# Laser_Driver_v6_1.net
KiCad netlist of a schematic drawn in Altium Designer
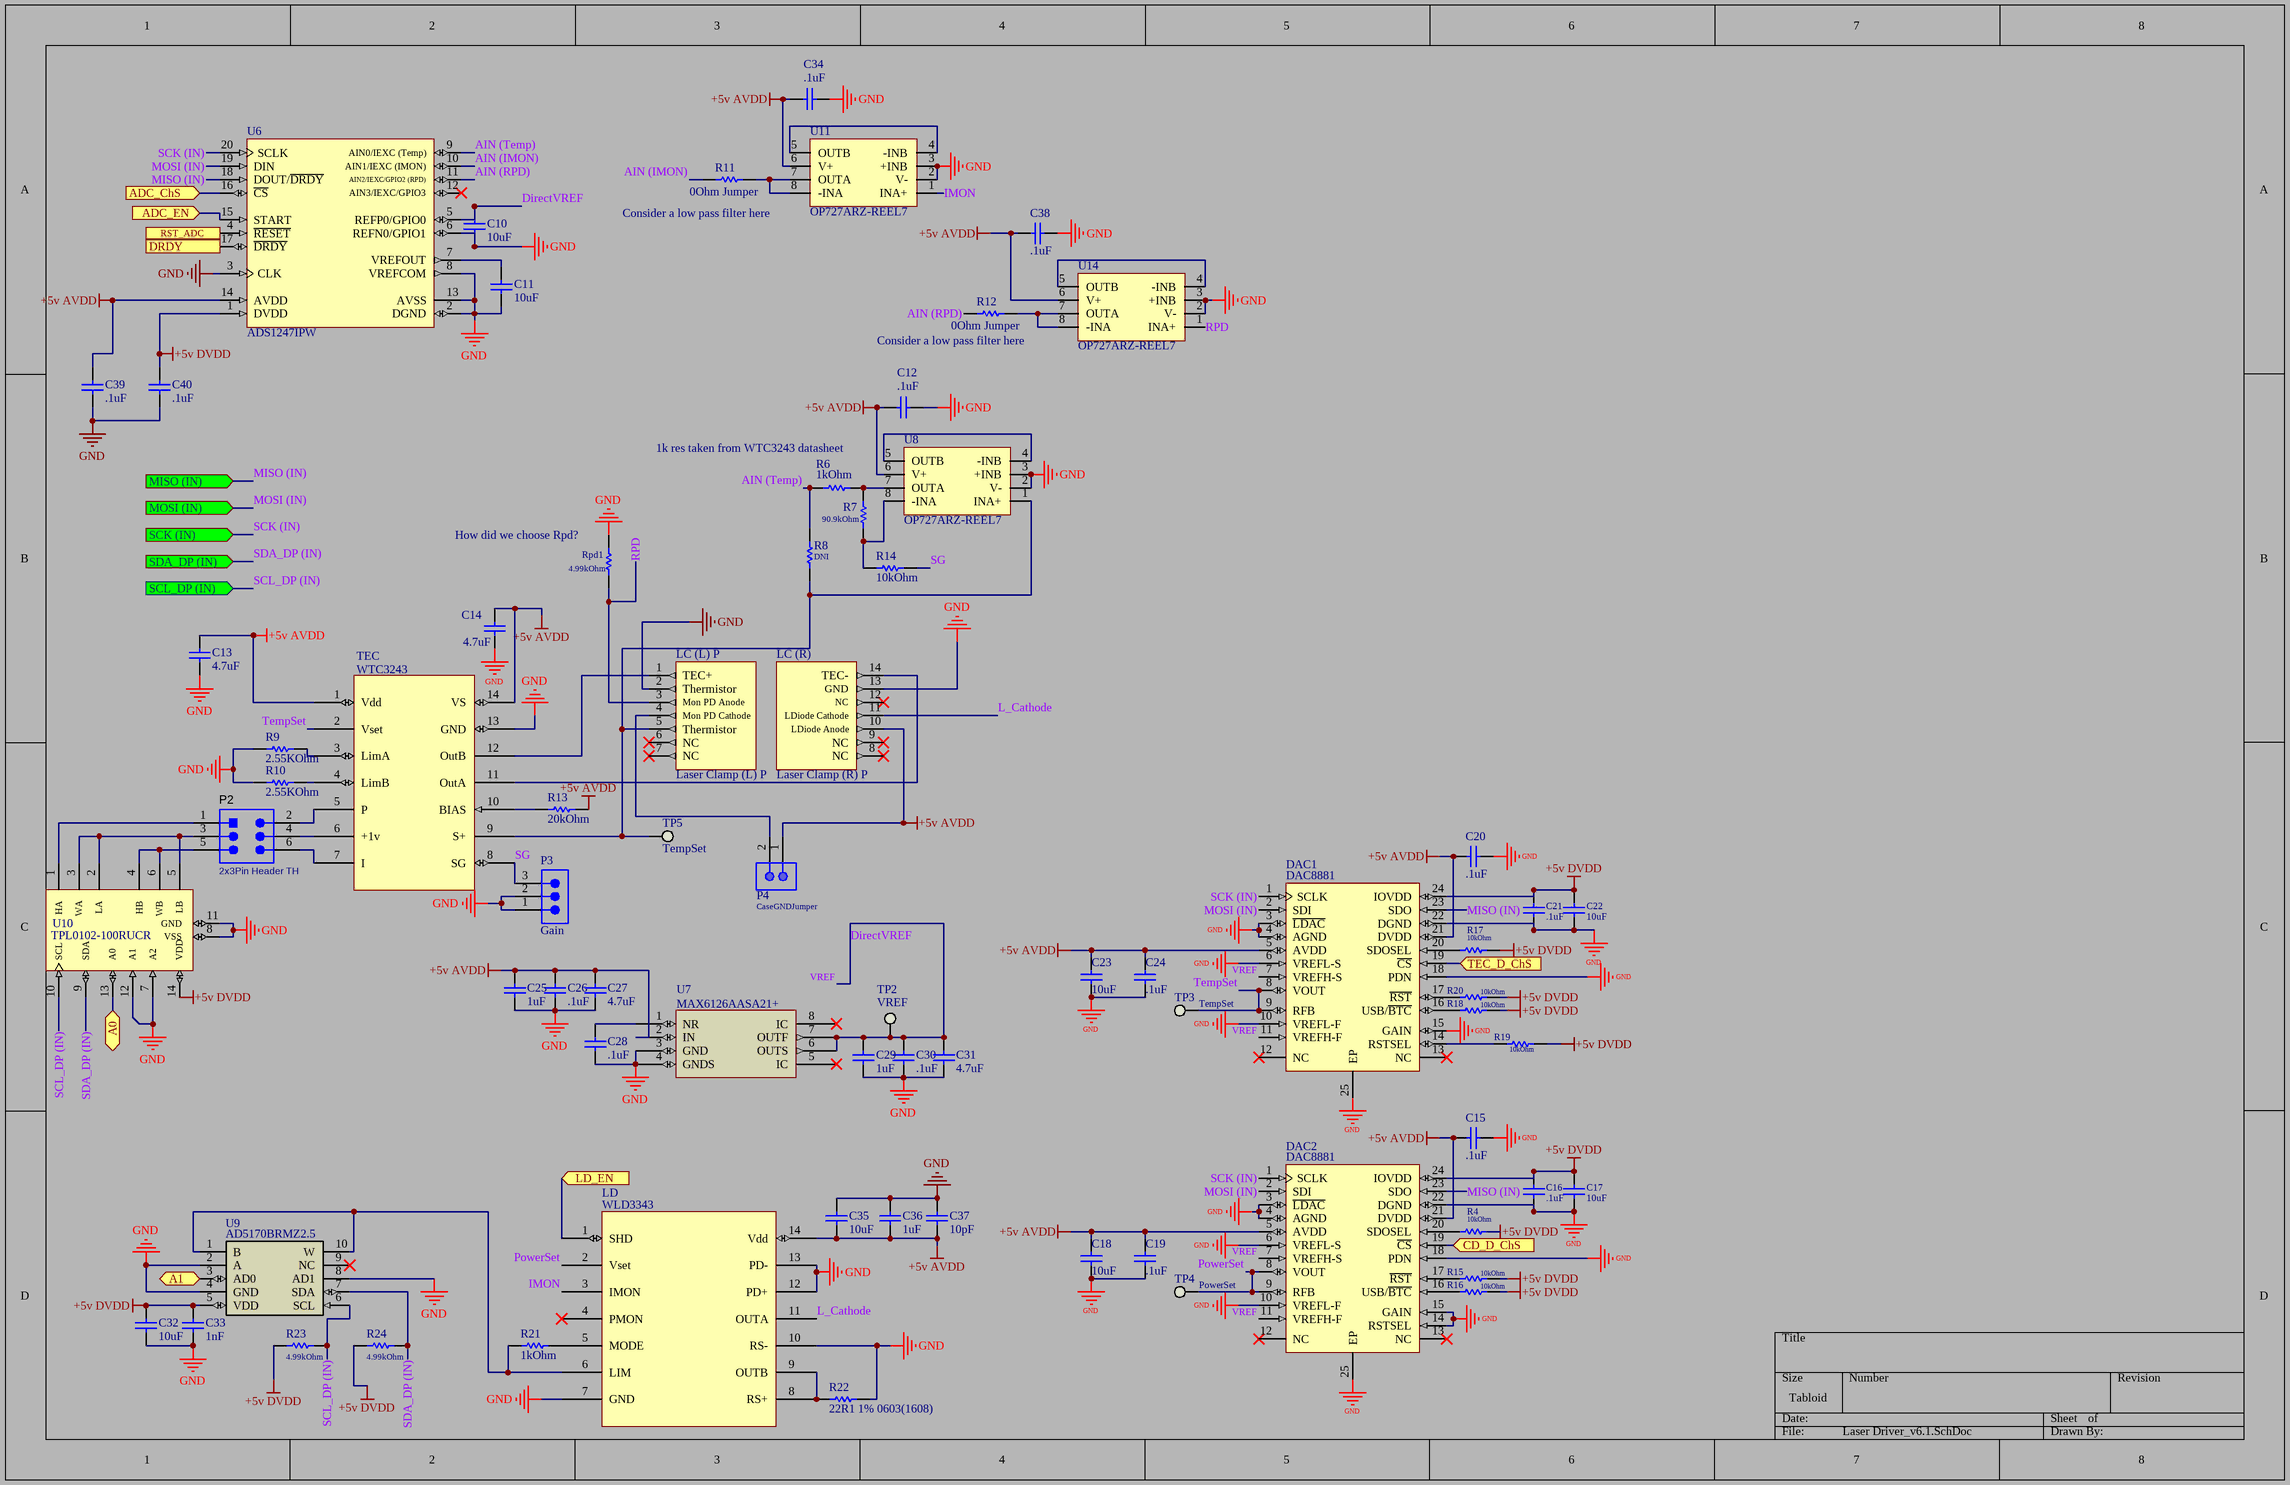
[diagram p0: Laser Driver_v6.1.SchDoc]

(export (version "E")
  (design (tool "Eeschema 10.0.6"))
  (components
    (comp (ref "C10")
      (value "10uF")
      (footprint "CAPC1608X90X35ML10T15")
      (fields (field (name "PART NUMBER") "GRM188R60G106ME47J") (field (name "MANUFACTURER") "Murata"))
      (libsource (lib "10uF Cap 0603") (part "CMP-2006-02549-1"))
    )
    (comp (ref "C11")
      (value "10uF")
      (footprint "CAPC1608X90X35ML10T15")
      (fields (field (name "PART NUMBER") "GRM188R60G106ME47J") (field (name "MANUFACTURER") "Murata"))
      (libsource (lib "10uF Cap 0603") (part "CMP-2006-02549-1"))
    )
    (comp (ref "C12")
      (value ".1uF")
      (footprint "CAPC1608X90X35ML15T15")
      (fields
        (field (name "PART NUMBER") "06033D104MAT2A")
        (field (name "MANUFACTURER") "AVX Interconnect / Elco")
      )
      (libsource (lib "0.1uF Cap 0603") (part "CMP-2006-04192-1"))
    )
    (comp (ref "C13")
      (value "4.7uF")
      (footprint "CAPC1608X90X35ML10T15")
      (description "Chip Capacitor, 4.7 uF, +/- 10%, 6.3 V, -55 to 85 degC, 0603 (1608 Metric), RoHS, Tape and Reel")
      (fields (field (name "PARTNUMBER") "GRM188R60J475KE19D") (field (name "TOLERANCE") "10%"))
      (libsource (lib "4.7uF Cap 0603") (part "CMP-2006-02799-2"))
    )
    (comp (ref "C14")
      (value "4.7uF")
      (footprint "CAPC1608X90X35ML10T15")
      (description "Chip Capacitor, 4.7 uF, +/- 10%, 6.3 V, -55 to 85 degC, 0603 (1608 Metric), RoHS, Tape and Reel")
      (fields (field (name "PARTNUMBER") "GRM188R60J475KE19D") (field (name "TOLERANCE") "10%"))
      (libsource (lib "4.7uF Cap 0603") (part "CMP-2006-02799-2"))
    )
    (comp (ref "C15")
      (value ".1uF")
      (footprint "CAPC1608X90X35ML15T15")
      (fields
        (field (name "PART NUMBER") "06033D104MAT2A")
        (field (name "MANUFACTURER") "AVX Interconnect / Elco")
      )
      (libsource (lib "0.1uF Cap 0603") (part "CMP-2006-04192-1"))
    )
    (comp (ref "C16")
      (value ".1uF")
      (footprint "CAPC1608X90X35ML15T15")
      (fields
        (field (name "PART NUMBER") "06033D104MAT2A")
        (field (name "MANUFACTURER") "AVX Interconnect / Elco")
      )
      (libsource (lib "0.1uF Cap 0603") (part "CMP-2006-04192-1"))
    )
    (comp (ref "C17")
      (value "10uF")
      (footprint "CAPC1608X90X35ML10T15")
      (fields (field (name "PART NUMBER") "GRM188R60G106ME47J") (field (name "MANUFACTURER") "Murata"))
      (libsource (lib "10uF Cap 0603") (part "CMP-2006-02549-1"))
    )
    (comp (ref "C18")
      (value "10uF")
      (footprint "CAPC1608X90X35ML10T15")
      (fields (field (name "PART NUMBER") "GRM188R60G106ME47J") (field (name "MANUFACTURER") "Murata"))
      (libsource (lib "10uF Cap 0603") (part "CMP-2006-02549-1"))
    )
    (comp (ref "C19")
      (value ".1uF")
      (footprint "CAPC1608X90X35ML15T15")
      (fields
        (field (name "PART NUMBER") "06033D104MAT2A")
        (field (name "MANUFACTURER") "AVX Interconnect / Elco")
      )
      (libsource (lib "0.1uF Cap 0603") (part "CMP-2006-04192-1"))
    )
    (comp (ref "C20")
      (value ".1uF")
      (footprint "CAPC1608X90X35ML15T15")
      (fields
        (field (name "PART NUMBER") "06033D104MAT2A")
        (field (name "MANUFACTURER") "AVX Interconnect / Elco")
      )
      (libsource (lib "0.1uF Cap 0603") (part "CMP-2006-04192-1"))
    )
    (comp (ref "C21")
      (value ".1uF")
      (footprint "CAPC1608X90X35ML15T15")
      (fields
        (field (name "PART NUMBER") "06033D104MAT2A")
        (field (name "MANUFACTURER") "AVX Interconnect / Elco")
      )
      (libsource (lib "0.1uF Cap 0603") (part "CMP-2006-04192-1"))
    )
    (comp (ref "C22")
      (value "10uF")
      (footprint "CAPC1608X90X35ML10T15")
      (fields (field (name "PART NUMBER") "GRM188R60G106ME47J") (field (name "MANUFACTURER") "Murata"))
      (libsource (lib "10uF Cap 0603") (part "CMP-2006-02549-1"))
    )
    (comp (ref "C23")
      (value "10uF")
      (footprint "CAPC1608X90X35ML10T15")
      (fields (field (name "PART NUMBER") "GRM188R60G106ME47J") (field (name "MANUFACTURER") "Murata"))
      (libsource (lib "10uF Cap 0603") (part "CMP-2006-02549-1"))
    )
    (comp (ref "C24")
      (value ".1uF")
      (footprint "CAPC1608X90X35ML15T15")
      (fields
        (field (name "PART NUMBER") "06033D104MAT2A")
        (field (name "MANUFACTURER") "AVX Interconnect / Elco")
      )
      (libsource (lib "0.1uF Cap 0603") (part "CMP-2006-04192-1"))
    )
    (comp (ref "C25")
      (value "1uF")
      (footprint "CAPC1608X90X35ML15T15")
      (fields
        (field (name "PART NUMBER") "06036D105KAT2A")
        (field (name "MANUFACTURER") "AVX Interconnect / Elco")
      )
      (libsource (lib "1uF Cap 0603") (part "CMP-2006-04474-1"))
    )
    (comp (ref "C26")
      (value ".1uF")
      (footprint "CAPC1608X90X35ML15T15")
      (fields
        (field (name "PART NUMBER") "06033D104MAT2A")
        (field (name "MANUFACTURER") "AVX Interconnect / Elco")
      )
      (libsource (lib "0.1uF Cap 0603") (part "CMP-2006-04192-1"))
    )
    (comp (ref "C27")
      (value "4.7uF")
      (footprint "CAPC1608X90X35ML10T15")
      (description "Chip Capacitor, 4.7 uF, +/- 10%, 6.3 V, -55 to 85 degC, 0603 (1608 Metric), RoHS, Tape and Reel")
      (fields (field (name "PARTNUMBER") "GRM188R60J475KE19D") (field (name "TOLERANCE") "10%"))
      (libsource (lib "4.7uF Cap 0603") (part "CMP-2006-02799-2"))
    )
    (comp (ref "C28")
      (value ".1uF")
      (footprint "CAPC1608X90X35ML15T15")
      (fields
        (field (name "PART NUMBER") "06033D104MAT2A")
        (field (name "MANUFACTURER") "AVX Interconnect / Elco")
      )
      (libsource (lib "0.1uF Cap 0603") (part "CMP-2006-04192-1"))
    )
    (comp (ref "C29")
      (value "1uF")
      (footprint "CAPC1608X90X35ML15T15")
      (fields
        (field (name "PART NUMBER") "06036D105KAT2A")
        (field (name "MANUFACTURER") "AVX Interconnect / Elco")
      )
      (libsource (lib "1uF Cap 0603") (part "CMP-2006-04474-1"))
    )
    (comp (ref "C30")
      (value ".1uF")
      (footprint "CAPC1608X90X35ML15T15")
      (fields
        (field (name "PART NUMBER") "06033D104MAT2A")
        (field (name "MANUFACTURER") "AVX Interconnect / Elco")
      )
      (libsource (lib "0.1uF Cap 0603") (part "CMP-2006-04192-1"))
    )
    (comp (ref "C31")
      (value "4.7uF")
      (footprint "CAPC1608X90X35ML10T15")
      (description "Chip Capacitor, 4.7 uF, +/- 10%, 6.3 V, -55 to 85 degC, 0603 (1608 Metric), RoHS, Tape and Reel")
      (fields (field (name "PARTNUMBER") "GRM188R60J475KE19D") (field (name "TOLERANCE") "10%"))
      (libsource (lib "4.7uF Cap 0603") (part "CMP-2006-02799-2"))
    )
    (comp (ref "C32")
      (value "10uF")
      (footprint "CAPC1608X90X35ML10T15")
      (fields (field (name "PART NUMBER") "GRM188R60G106ME47J") (field (name "MANUFACTURER") "Murata"))
      (libsource (lib "10uF Cap 0603") (part "CMP-2006-02549-1"))
    )
    (comp (ref "C33")
      (value "1nF")
      (footprint "CAPC1608X90X35LL15T15")
      (fields
        (field (name "MANUFACTURER") "AVX Interconnect / Elco")
        (field (name "PART NUMBER") "06035C102KAT2A")
      )
      (libsource (lib "Altium Content Vault") (part "CAP"))
    )
    (comp (ref "C34")
      (value ".1uF")
      (footprint "CAPC1608X90X35ML15T15")
      (fields
        (field (name "PART NUMBER") "06033D104MAT2A")
        (field (name "MANUFACTURER") "AVX Interconnect / Elco")
      )
      (libsource (lib "0.1uF Cap 0603") (part "CMP-2006-04192-1"))
    )
    (comp (ref "C35")
      (value "10uF")
      (footprint "CAPC1608X90X35ML10T15")
      (fields (field (name "PART NUMBER") "GRM188R60G106ME47J") (field (name "MANUFACTURER") "Murata"))
      (libsource (lib "10uF Cap 0603") (part "CMP-2006-02549-1"))
    )
    (comp (ref "C36")
      (value "1uF")
      (footprint "CAPC1608X90X35ML15T15")
      (fields
        (field (name "PART NUMBER") "06036D105KAT2A")
        (field (name "MANUFACTURER") "AVX Interconnect / Elco")
      )
      (libsource (lib "1uF Cap 0603") (part "CMP-2006-04474-1"))
    )
    (comp (ref "C37")
      (value "10pF")
      (footprint "CAPC1608X90X35LL15T15")
      (fields
        (field (name "MANUFACTURER") "AVX Interconnect / Elco")
        (field (name "PART NUMBER") "06035A100DAT2A")
      )
      (libsource (lib "Altium Content Vault") (part "CAP"))
    )
    (comp (ref "C38")
      (value ".1uF")
      (footprint "CAPC1608X90X35ML15T15")
      (fields
        (field (name "PART NUMBER") "06033D104MAT2A")
        (field (name "MANUFACTURER") "AVX Interconnect / Elco")
      )
      (libsource (lib "0.1uF Cap 0603") (part "CMP-2006-04192-1"))
    )
    (comp (ref "C39")
      (value ".1uF")
      (footprint "CAPC1608X90X35ML15T15")
      (fields
        (field (name "PART NUMBER") "06033D104MAT2A")
        (field (name "MANUFACTURER") "AVX Interconnect / Elco")
      )
      (libsource (lib "0.1uF Cap 0603") (part "CMP-2006-04192-1"))
    )
    (comp (ref "C40")
      (value ".1uF")
      (footprint "CAPC1608X90X35ML15T15")
      (fields
        (field (name "PART NUMBER") "06033D104MAT2A")
        (field (name "MANUFACTURER") "AVX Interconnect / Elco")
      )
      (libsource (lib "0.1uF Cap 0603") (part "CMP-2006-04192-1"))
    )
    (comp (ref "DAC1")
      (value "DAC8881")
      (footprint "TI-RGE24-2450X2450TP_V")
      (fields (field (name "PARTNUMBER") "DAC8881SRGET") (field (name "MANUFACTURER") "Texas Instruments"))
      (libsource (lib "DAC8881") (part "CMP-0004-01437-1"))
    )
    (comp (ref "DAC2")
      (value "DAC8881")
      (footprint "TI-RGE24-2450X2450TP_V")
      (fields (field (name "PARTNUMBER") "DAC8881SRGET") (field (name "MANUFACTURER") "Texas Instruments"))
      (libsource (lib "DAC8881") (part "CMP-0004-01437-1"))
    )
    (comp (ref "LC (L) P")
      (value "Laser Clamp (L) P")
      (footprint "LaserClamp_L_Pump")
      (libsource (lib "LDv6") (part "Laser Clamp (L) Pump"))
    )
    (comp (ref "LC (R)")
      (value "Laser Clamp (R) P")
      (footprint "LaserClamp_R_Pump")
      (libsource (lib "LDv6") (part "Laser Clamp (R) Pump"))
    )
    (comp (ref "LD")
      (value "WLD3343")
      (footprint "LDv6:WLD3343")
      (description "Laser Current Driver")
      (libsource (lib "LDv6") (part "WLD3343"))
    )
    (comp (ref "P2")
      (value "2x3Pin Header TH")
      (footprint "SMTC-TSW-103-07-G-D_V")
      (fields (field (name "MANUFACTURER") "Samtec-Inc."))
      (libsource (lib "2x3 Pin Header TH 2.54") (part "CMP-2000-07329-1"))
    )
    (comp (ref "P3")
      (value "Gain")
      (footprint "SMTC-TSW-103-07-X-S")
      (description "0.025\" SQ Post Header, Through-hole, Vertical, -55 to 125 degC, 2.54 mm Pitch, 3-Pin, Male, RoHS")
      (fields (field (name "MANUFACTURER") "Samtec") (field (name "PARTNUMBER") "TSW-103-07-F-S"))
      (libsource (lib "3 Pin Header TH 2.54") (part "CMP-1024-00331-1"))
    )
    (comp (ref "P4")
      (value "CaseGNDJumper")
      (footprint "SMTC-TSW-102-07-S-S")
      (fields (field (name "MANUFACTURER") "Samtec"))
      (libsource (lib "2 Pin Header TH 2.54") (part "CMP-1681-00004-4"))
    )
    (comp (ref "R4")
      (value "10kOhm")
      (footprint "RESC1609X55X30LL15T15")
      (description "Chip Resistor, 10 KOhm, +/- 1%, 0.1 W, -55 to 155 degC, 0603 (1608 Metric), RoHS, Tape and Reel")
      (fields (field (name "TOLERANCE") "1%") (field (name "MANUFACTURER") "Panasonic"))
      (libsource (lib "10kOhm Res 0603") (part "CMP-2000-07452-1"))
    )
    (comp (ref "R6")
      (value "1kOhm")
      (footprint "RESC1609X50X30LL8T20")
      (description "Chip Resistor, 1 KOhm, +/- 1%, 0.1 W, -55 to 155 degC, 0603 (1608 Metric), RoHS, Tape and Reel")
      (fields (field (name "MANUFACTURER") "Vishay Semiconductor"))
      (libsource (lib "1kOhm Res 0603") (part "CMP-1666-00003-4"))
    )
    (comp (ref "R7")
      (value "90.9kOhm")
      (footprint "RESC1608X55X30NL15T15")
      (fields (field (name "MANUFACTURER") "Panasonic") (field (name "PART NUMBER") "ERJ-3EKF9092V"))
      (libsource (lib "90.9kOhm Res 0603") (part "CMP-2000-00680-1"))
    )
    (comp (ref "R8")
      (value "DNI")
      (footprint "RESC1608X55X25NL10T15")
      (description "Chip Resistor, 0 Ohm, +/- 5%, 0.1 W, -55 to 155 degC, 0603 (1608 Metric), RoHS, Tape and Reel")
      (fields (field (name "TOLERANCE") "5%") (field (name "MANUFACTURER") "Yageo"))
      (libsource (lib "0Ohm Jumper 0603") (part "CMP-2100-03667-1"))
    )
    (comp (ref "R9")
      (value "2.55KOhm")
      (footprint "RESC1608X55X25NL10T15")
      (fields (field (name "MANUFACTURER") "Yageo") (field (name "PART NUMBER") "RC0603FR-072K55L"))
      (libsource (lib "Altium Content Vault") (part "RES"))
    )
    (comp (ref "R10")
      (value "2.55KOhm")
      (footprint "RESC1608X55X25NL10T15")
      (fields (field (name "MANUFACTURER") "Yageo") (field (name "PART NUMBER") "RC0603FR-072K55L"))
      (libsource (lib "Altium Content Vault") (part "RES"))
    )
    (comp (ref "R11")
      (value "0Ohm Jumper")
      (footprint "RESC1608X55X25NL10T15")
      (description "Chip Resistor, 0 Ohm, +/- 5%, 0.1 W, -55 to 155 degC, 0603 (1608 Metric), RoHS, Tape and Reel")
      (fields (field (name "TOLERANCE") "5%") (field (name "MANUFACTURER") "Yageo"))
      (libsource (lib "0Ohm Jumper 0603") (part "CMP-2100-03667-1"))
    )
    (comp (ref "R12")
      (value "0Ohm Jumper")
      (footprint "RESC1608X55X25NL10T15")
      (description "Chip Resistor, 0 Ohm, +/- 5%, 0.1 W, -55 to 155 degC, 0603 (1608 Metric), RoHS, Tape and Reel")
      (fields (field (name "TOLERANCE") "5%") (field (name "MANUFACTURER") "Yageo"))
      (libsource (lib "0Ohm Jumper 0603") (part "CMP-2100-03667-1"))
    )
    (comp (ref "R13")
      (value "20kOhm")
      (footprint "RESC1608X55X25NL10T15")
      (description "Chip Resistor, 20 KOhm, +/- 1%, 0.1 W, -55 to 155 degC, 0603 (1608 Metric), RoHS, Tape and Reel")
      (fields (field (name "MANUFACTURER") "Yageo") (field (name "TOLERANCE") "1%"))
      (libsource (lib "20kOhm Res 0603") (part "CMP-2000-06932-1"))
    )
    (comp (ref "R14")
      (value "10kOhm")
      (footprint "RESC1609X55X30LL15T15")
      (description "Chip Resistor, 10 KOhm, +/- 1%, 0.1 W, -55 to 155 degC, 0603 (1608 Metric), RoHS, Tape and Reel")
      (fields (field (name "TOLERANCE") "1%") (field (name "MANUFACTURER") "Panasonic"))
      (libsource (lib "10kOhm Res 0603") (part "CMP-2000-07452-1"))
    )
    (comp (ref "R15")
      (value "10kOhm")
      (footprint "RESC1609X55X30LL15T15")
      (description "Chip Resistor, 10 KOhm, +/- 1%, 0.1 W, -55 to 155 degC, 0603 (1608 Metric), RoHS, Tape and Reel")
      (fields (field (name "TOLERANCE") "1%") (field (name "MANUFACTURER") "Panasonic"))
      (libsource (lib "10kOhm Res 0603") (part "CMP-2000-07452-1"))
    )
    (comp (ref "R16")
      (value "10kOhm")
      (footprint "RESC1609X55X30LL15T15")
      (description "Chip Resistor, 10 KOhm, +/- 1%, 0.1 W, -55 to 155 degC, 0603 (1608 Metric), RoHS, Tape and Reel")
      (fields (field (name "TOLERANCE") "1%") (field (name "MANUFACTURER") "Panasonic"))
      (libsource (lib "10kOhm Res 0603") (part "CMP-2000-07452-1"))
    )
    (comp (ref "R17")
      (value "10kOhm")
      (footprint "RESC1609X55X30LL15T15")
      (description "Chip Resistor, 10 KOhm, +/- 1%, 0.1 W, -55 to 155 degC, 0603 (1608 Metric), RoHS, Tape and Reel")
      (fields (field (name "TOLERANCE") "1%") (field (name "MANUFACTURER") "Panasonic"))
      (libsource (lib "10kOhm Res 0603") (part "CMP-2000-07452-1"))
    )
    (comp (ref "R18")
      (value "10kOhm")
      (footprint "RESC1609X55X30LL15T15")
      (description "Chip Resistor, 10 KOhm, +/- 1%, 0.1 W, -55 to 155 degC, 0603 (1608 Metric), RoHS, Tape and Reel")
      (fields (field (name "TOLERANCE") "1%") (field (name "MANUFACTURER") "Panasonic"))
      (libsource (lib "10kOhm Res 0603") (part "CMP-2000-07452-1"))
    )
    (comp (ref "R19")
      (value "10kOhm")
      (footprint "RESC1609X55X30LL15T15")
      (description "Chip Resistor, 10 KOhm, +/- 1%, 0.1 W, -55 to 155 degC, 0603 (1608 Metric), RoHS, Tape and Reel")
      (fields (field (name "TOLERANCE") "1%") (field (name "MANUFACTURER") "Panasonic"))
      (libsource (lib "10kOhm Res 0603") (part "CMP-2000-07452-1"))
    )
    (comp (ref "R20")
      (value "10kOhm")
      (footprint "RESC1609X55X30LL15T15")
      (description "Chip Resistor, 10 KOhm, +/- 1%, 0.1 W, -55 to 155 degC, 0603 (1608 Metric), RoHS, Tape and Reel")
      (fields (field (name "TOLERANCE") "1%") (field (name "MANUFACTURER") "Panasonic"))
      (libsource (lib "10kOhm Res 0603") (part "CMP-2000-07452-1"))
    )
    (comp (ref "R21")
      (value "1kOhm")
      (footprint "RESC1609X50X30LL8T20")
      (description "Chip Resistor, 1 KOhm, +/- 1%, 0.1 W, -55 to 155 degC, 0603 (1608 Metric), RoHS, Tape and Reel")
      (fields (field (name "MANUFACTURER") "Vishay Semiconductor"))
      (libsource (lib "1kOhm Res 0603") (part "CMP-1666-00003-4"))
    )
    (comp (ref "R22")
      (value "22R1 1% 0603(1608)")
      (footprint "RESC0603(1608)_M")
      (description "22R1 0.1W 1% 0603 (1608 Metric)  SMD")
      (fields (field (name "TOLERANCE") "1 %") (field (name "POWER") "0.1 W"))
      (libsource (lib "Altium Content Vault") (part "RES"))
    )
    (comp (ref "R23")
      (value "4.99kOhm")
      (footprint "RESC1608X55X30NL15T15")
      (fields (field (name "PART NUMBER") "ERJ-3EKF4991V") (field (name "MANUFACTURER") "Panasonic"))
      (libsource (lib "4.99kOhm Res 0603") (part "CMP-2000-00535-1"))
    )
    (comp (ref "R24")
      (value "4.99kOhm")
      (footprint "RESC1608X55X30NL15T15")
      (fields (field (name "PART NUMBER") "ERJ-3EKF4991V") (field (name "MANUFACTURER") "Panasonic"))
      (libsource (lib "4.99kOhm Res 0603") (part "CMP-2000-00535-1"))
    )
    (comp (ref "Rpd1")
      (value "4.99kOhm")
      (footprint "RESC1608X55X30NL15T15")
      (fields (field (name "PART NUMBER") "ERJ-3EKF4991V") (field (name "MANUFACTURER") "Panasonic"))
      (libsource (lib "4.99kOhm Res 0603") (part "CMP-2000-00535-1"))
    )
    (comp (ref "TEC")
      (value "WTC3243")
      (footprint "WTC3243")
      (description "TEC")
      (libsource (lib "LDv6") (part "WTC3243"))
    )
    (comp (ref "TP2")
      (value "VREF")
      (footprint "KSTN-5015_V")
      (description "Test Point, White, SMT")
      (fields (field (name "MANUFACTURER") "Keystone"))
      (libsource (lib "Test Point 2.66mm") (part "CMP-2000-05183-1"))
    )
    (comp (ref "TP3")
      (value "TempSet")
      (footprint "KSTN-5015_V")
      (description "Test Point, White, SMT")
      (fields (field (name "MANUFACTURER") "Keystone"))
      (libsource (lib "Test Point 2.66mm") (part "CMP-2000-05183-1"))
    )
    (comp (ref "TP4")
      (value "PowerSet")
      (footprint "KSTN-5015_V")
      (description "Test Point, White, SMT")
      (fields (field (name "MANUFACTURER") "Keystone"))
      (libsource (lib "Test Point 2.66mm") (part "CMP-2000-05183-1"))
    )
    (comp (ref "TP5")
      (value "TempSet")
      (footprint "KSTN-5015_V")
      (description "Test Point, White, SMT")
      (fields (field (name "MANUFACTURER") "Keystone"))
      (libsource (lib "Test Point 2.66mm") (part "CMP-2000-05183-1"))
    )
    (comp (ref "U6")
      (value "ADS1247IPW")
      (footprint "TI-PW20_N")
      (description "Low Noise, Precision 24-Bit ADC, -40 to 105 degC, 20-pin SOP (PW20), Green (RoHS & no Sb/Br)")
      (fields (field (name "MANUFACTURER") "Texas Instruments"))
      (libsource (lib "ADS1247") (part "CMP-0003-00815-2"))
    )
    (comp (ref "U7")
      (value "MAX6126AASA21+")
      (footprint "21-0041B_8")
      (description "No Description Available")
      (fields (field (name "COPYRIGHT") "Copyright (C) 2018 Accelerated Designs. All rights reserved"))
      (libsource (lib "MAX6126AASA21") (part "MAX6126AASA21+"))
    )
    (comp (ref "U8")
      (value "OP727ARZ-REEL7")
      (footprint "ADI-R-8_L")
      (fields (field (name "MANUFACTURER") "Analog Devices") (field (name "GENERIC PART NUMBER") "OP727"))
      (libsource (lib "OP727ARZ") (part "CMP-0384-00653-1"))
    )
    (comp (ref "U9")
      (value "AD5170BRMZ2.5")
      (footprint "RM_10")
      (description "No Description Available")
      (fields (field (name "COPYRIGHT") "Copyright (C) 2016 Accelerated Designs. All rights reserved"))
      (libsource (lib "AD5170 Digital Pot 2.5kOhm") (part "AD5170BRMZ2.5"))
    )
    (comp (ref "U10")
      (value "TPL0102-100RUCR")
      (footprint "TI-RUC14_V")
      (fields (field (name "MANUFACTURER") "Texas Instruments"))
      (libsource (lib "TPL0102") (part "CMP-0004-01517-1"))
    )
    (comp (ref "U11")
      (value "OP727ARZ-REEL7")
      (footprint "ADI-R-8_L")
      (fields (field (name "MANUFACTURER") "Analog Devices") (field (name "GENERIC PART NUMBER") "OP727"))
      (libsource (lib "OP727ARZ") (part "CMP-0384-00653-1"))
    )
    (comp (ref "U14")
      (value "OP727ARZ-REEL7")
      (footprint "ADI-R-8_L")
      (fields (field (name "MANUFACTURER") "Analog Devices") (field (name "GENERIC PART NUMBER") "OP727"))
      (libsource (lib "OP727ARZ") (part "CMP-0384-00653-1"))
    )
  )
  (nets
    (net (code "1") (name "+5v AVDD") (class "Default")
      (node (ref "C12") (pin "1") (pinfunction "1_1") (pintype "passive"))
      (node (ref "C13") (pin "2") (pinfunction "2_2") (pintype "passive"))
      (node (ref "C14") (pin "2") (pinfunction "2_2") (pintype "passive"))
      (node (ref "C15") (pin "1") (pinfunction "1_1") (pintype "passive"))
      (node (ref "C18") (pin "1") (pinfunction "1_1") (pintype "passive"))
      (node (ref "C19") (pin "1") (pinfunction "1_1") (pintype "passive"))
      (node (ref "C20") (pin "1") (pinfunction "1_1") (pintype "passive"))
      (node (ref "C23") (pin "1") (pinfunction "1_1") (pintype "passive"))
      (node (ref "C24") (pin "1") (pinfunction "1_1") (pintype "passive"))
      (node (ref "C25") (pin "2") (pinfunction "2_2") (pintype "passive"))
      (node (ref "C26") (pin "2") (pinfunction "2_2") (pintype "passive"))
      (node (ref "C27") (pin "2") (pinfunction "2_2") (pintype "passive"))
      (node (ref "C34") (pin "1") (pinfunction "1_1") (pintype "passive"))
      (node (ref "C35") (pin "1") (pinfunction "1_1") (pintype "passive"))
      (node (ref "C36") (pin "2") (pinfunction "2_2") (pintype "passive"))
      (node (ref "C37") (pin "1") (pinfunction "1_1") (pintype "passive"))
      (node (ref "C38") (pin "1") (pinfunction "1_1") (pintype "passive"))
      (node (ref "C39") (pin "2") (pinfunction "2_2") (pintype "passive"))
      (node (ref "DAC1") (pin "21") (pinfunction "DVDD_21") (pintype "bidirectional"))
      (node (ref "DAC1") (pin "5") (pinfunction "AVDD_5") (pintype "bidirectional"))
      (node (ref "DAC2") (pin "21") (pinfunction "DVDD_21") (pintype "bidirectional"))
      (node (ref "DAC2") (pin "5") (pinfunction "AVDD_5") (pintype "bidirectional"))
      (node (ref "LC (R)") (pin "10") (pinfunction "LDiode_Anode_10") (pintype "output"))
      (node (ref "LD") (pin "14") (pinfunction "Vdd_14") (pintype "bidirectional"))
      (node (ref "P4") (pin "1") (pinfunction "1_1") (pintype "passive"))
      (node (ref "R13") (pin "2") (pinfunction "2_2") (pintype "passive"))
      (node (ref "TEC") (pin "1") (pinfunction "Vdd_1") (pintype "bidirectional"))
      (node (ref "TEC") (pin "14") (pinfunction "VS_14") (pintype "bidirectional"))
      (node (ref "U11") (pin "6") (pinfunction "V+_6") (pintype "passive"))
      (node (ref "U14") (pin "6") (pinfunction "V+_6") (pintype "passive"))
      (node (ref "U6") (pin "14") (pinfunction "AVDD_14") (pintype "input"))
      (node (ref "U7") (pin "2") (pinfunction "IN_2") (pintype "bidirectional"))
      (node (ref "U8") (pin "6") (pinfunction "V+_6") (pintype "passive"))
    )
    (net (code "2") (name "+5v DVDD") (class "Default")
      (node (ref "C16") (pin "2") (pinfunction "2_2") (pintype "passive"))
      (node (ref "C17") (pin "2") (pinfunction "2_2") (pintype "passive"))
      (node (ref "C21") (pin "2") (pinfunction "2_2") (pintype "passive"))
      (node (ref "C22") (pin "2") (pinfunction "2_2") (pintype "passive"))
      (node (ref "C32") (pin "2") (pinfunction "2_2") (pintype "passive"))
      (node (ref "C33") (pin "2") (pinfunction "2_2") (pintype "passive"))
      (node (ref "C40") (pin "2") (pinfunction "2_2") (pintype "passive"))
      (node (ref "DAC1") (pin "24") (pinfunction "IOVDD_24") (pintype "bidirectional"))
      (node (ref "DAC2") (pin "24") (pinfunction "IOVDD_24") (pintype "bidirectional"))
      (node (ref "R15") (pin "2") (pinfunction "2_2") (pintype "passive"))
      (node (ref "R16") (pin "2") (pinfunction "2_2") (pintype "passive"))
      (node (ref "R17") (pin "2") (pinfunction "2_2") (pintype "passive"))
      (node (ref "R18") (pin "2") (pinfunction "2_2") (pintype "passive"))
      (node (ref "R19") (pin "2") (pinfunction "2_2") (pintype "passive"))
      (node (ref "R20") (pin "2") (pinfunction "2_2") (pintype "passive"))
      (node (ref "R23") (pin "1") (pinfunction "1_1") (pintype "passive"))
      (node (ref "R24") (pin "1") (pinfunction "1_1") (pintype "passive"))
      (node (ref "R4") (pin "2") (pinfunction "2_2") (pintype "passive"))
      (node (ref "U10") (pin "14") (pinfunction "VDD_14") (pintype "bidirectional"))
      (node (ref "U6") (pin "1") (pinfunction "DVDD_1") (pintype "input"))
      (node (ref "U9") (pin "5") (pinfunction "VDD_5") (pintype "bidirectional"))
    )
    (net (code "3") (name "/A0") (class "Default")
      (node (ref "U10") (pin "13") (pinfunction "A0_13") (pintype "bidirectional"))
    )
    (net (code "4") (name "/A1") (class "Default")
      (node (ref "U9") (pin "3") (pinfunction "AD0_3") (pintype "bidirectional"))
    )
    (net (code "5") (name "/ADC_ChS") (class "Default")
      (node (ref "U6") (pin "16") (pinfunction "~{CS}_16") (pintype "bidirectional"))
    )
    (net (code "6") (name "/ADC_EN") (class "Default")
      (node (ref "U6") (pin "15") (pinfunction "START_15") (pintype "input"))
    )
    (net (code "7") (name "/AIN (IMON)") (class "Default")
      (node (ref "R11") (pin "1") (pinfunction "1_1") (pintype "passive"))
      (node (ref "U6") (pin "10") (pinfunction "AIN1/IEXC_(IMON)_10") (pintype "bidirectional"))
    )
    (net (code "8") (name "/AIN (RPD)") (class "Default")
      (node (ref "R12") (pin "1") (pinfunction "1_1") (pintype "passive"))
      (node (ref "U6") (pin "11") (pinfunction "AIN2/IEXC/GPIO2_(RPD)_11") (pintype "bidirectional"))
    )
    (net (code "9") (name "/AIN (Temp)") (class "Default")
      (node (ref "R6") (pin "1") (pinfunction "1_1") (pintype "passive"))
      (node (ref "R8") (pin "2") (pinfunction "2_2") (pintype "passive"))
      (node (ref "U6") (pin "9") (pinfunction "AIN0/IEXC_(Temp)_9") (pintype "bidirectional"))
    )
    (net (code "10") (name "/CD_D_ChS") (class "Default")
      (node (ref "DAC2") (pin "19") (pinfunction "~{CS}_19") (pintype "input"))
    )
    (net (code "11") (name "/DRDY") (class "Default")
      (node (ref "U6") (pin "17") (pinfunction "~{DRDY}_17") (pintype "bidirectional"))
    )
    (net (code "12") (name "/DirectVREF") (class "Default")
      (node (ref "C10") (pin "2") (pinfunction "2_2") (pintype "passive"))
      (node (ref "C29") (pin "2") (pinfunction "2_2") (pintype "passive"))
      (node (ref "C30") (pin "2") (pinfunction "2_2") (pintype "passive"))
      (node (ref "C31") (pin "2") (pinfunction "2_2") (pintype "passive"))
      (node (ref "DAC1") (pin "11") (pinfunction "VREFH-F_11") (pintype "input"))
      (node (ref "DAC1") (pin "7") (pinfunction "VREFH-S_7") (pintype "input"))
      (node (ref "DAC2") (pin "11") (pinfunction "VREFH-F_11") (pintype "input"))
      (node (ref "DAC2") (pin "7") (pinfunction "VREFH-S_7") (pintype "input"))
      (node (ref "TP2") (pin "1") (pinfunction "1_1") (pintype "passive"))
      (node (ref "U6") (pin "5") (pinfunction "REFP0/GPIO0_5") (pintype "bidirectional"))
      (node (ref "U7") (pin "6") (pinfunction "OUTS_6") (pintype "output"))
      (node (ref "U7") (pin "7") (pinfunction "OUTF_7") (pintype "output"))
    )
    (net (code "13") (name "/IMON") (class "Default")
      (node (ref "LD") (pin "3") (pinfunction "IMON_3") (pintype "passive"))
      (node (ref "U11") (pin "1") (pinfunction "INA+_1") (pintype "passive"))
    )
    (net (code "14") (name "/LD_EN") (class "Default")
      (node (ref "LD") (pin "1") (pinfunction "SHD_1") (pintype "bidirectional"))
    )
    (net (code "15") (name "/L_Cathode") (class "Default")
      (node (ref "LC (R)") (pin "11") (pinfunction "LDiode_Cathode_11") (pintype "output"))
      (node (ref "LD") (pin "11") (pinfunction "OUTA_11") (pintype "passive"))
    )
    (net (code "16") (name "/MISO (IN)") (class "Default")
      (node (ref "DAC1") (pin "23") (pinfunction "SDO_23") (pintype "input"))
      (node (ref "DAC2") (pin "23") (pinfunction "SDO_23") (pintype "input"))
      (node (ref "U6") (pin "18") (pinfunction "DOUT/~{DRDY}_18") (pintype "input"))
    )
    (net (code "17") (name "/MOSI (IN)") (class "Default")
      (node (ref "DAC1") (pin "2") (pinfunction "SDI_2") (pintype "input"))
      (node (ref "DAC2") (pin "2") (pinfunction "SDI_2") (pintype "input"))
      (node (ref "U6") (pin "19") (pinfunction "DIN_19") (pintype "input"))
    )
    (net (code "18") (name "/PowerSet") (class "Default")
      (node (ref "DAC2") (pin "8") (pinfunction "VOUT_8") (pintype "bidirectional"))
      (node (ref "DAC2") (pin "9") (pinfunction "RFB_9") (pintype "bidirectional"))
      (node (ref "LD") (pin "2") (pinfunction "Vset_2") (pintype "passive"))
      (node (ref "TP4") (pin "1") (pinfunction "1_1") (pintype "passive"))
    )
    (net (code "19") (name "/RPD") (class "Default")
      (node (ref "LC (L) P") (pin "3") (pinfunction "Mon_PD_Anode_3") (pintype "output"))
      (node (ref "Rpd1") (pin "1") (pinfunction "1_1") (pintype "passive"))
      (node (ref "U14") (pin "1") (pinfunction "INA+_1") (pintype "passive"))
    )
    (net (code "20") (name "/RST_ADC") (class "Default")
      (node (ref "U6") (pin "4") (pinfunction "~{RESET}_4") (pintype "input"))
    )
    (net (code "21") (name "/SCK (IN)") (class "Default")
      (node (ref "DAC1") (pin "1") (pinfunction "SCLK_1") (pintype "input"))
      (node (ref "DAC2") (pin "1") (pinfunction "SCLK_1") (pintype "input"))
      (node (ref "U6") (pin "20") (pinfunction "SCLK_20") (pintype "input"))
    )
    (net (code "22") (name "/SCL_DP (IN)") (class "Default")
      (node (ref "R23") (pin "2") (pinfunction "2_2") (pintype "passive"))
      (node (ref "U10") (pin "10") (pinfunction "SCL_10") (pintype "input"))
      (node (ref "U9") (pin "6") (pinfunction "SCL_6") (pintype "input"))
    )
    (net (code "23") (name "/SDA_DP (IN)") (class "Default")
      (node (ref "R24") (pin "2") (pinfunction "2_2") (pintype "passive"))
      (node (ref "U10") (pin "9") (pinfunction "SDA_9") (pintype "bidirectional"))
      (node (ref "U9") (pin "7") (pinfunction "SDA_7") (pintype "bidirectional"))
    )
    (net (code "24") (name "/SG") (class "Default")
      (node (ref "P3") (pin "3") (pinfunction "3_3") (pintype "passive"))
      (node (ref "R14") (pin "2") (pinfunction "2_2") (pintype "passive"))
      (node (ref "TEC") (pin "8") (pinfunction "SG_8") (pintype "bidirectional"))
    )
    (net (code "25") (name "/TEC_D_ChS") (class "Default")
      (node (ref "DAC1") (pin "19") (pinfunction "~{CS}_19") (pintype "input"))
    )
    (net (code "26") (name "/TempSet") (class "Default")
      (node (ref "DAC1") (pin "8") (pinfunction "VOUT_8") (pintype "bidirectional"))
      (node (ref "DAC1") (pin "9") (pinfunction "RFB_9") (pintype "bidirectional"))
      (node (ref "TEC") (pin "2") (pinfunction "Vset_2") (pintype "passive"))
      (node (ref "TP3") (pin "1") (pinfunction "1_1") (pintype "passive"))
    )
    (net (code "27") (name "GND") (class "Default")
      (node (ref "C10") (pin "1") (pinfunction "1_1") (pintype "passive"))
      (node (ref "C11") (pin "1") (pinfunction "1_1") (pintype "passive"))
      (node (ref "C12") (pin "2") (pinfunction "2_2") (pintype "passive"))
      (node (ref "C13") (pin "1") (pinfunction "1_1") (pintype "passive"))
      (node (ref "C14") (pin "1") (pinfunction "1_1") (pintype "passive"))
      (node (ref "C15") (pin "2") (pinfunction "2_2") (pintype "passive"))
      (node (ref "C16") (pin "1") (pinfunction "1_1") (pintype "passive"))
      (node (ref "C17") (pin "1") (pinfunction "1_1") (pintype "passive"))
      (node (ref "C18") (pin "2") (pinfunction "2_2") (pintype "passive"))
      (node (ref "C19") (pin "2") (pinfunction "2_2") (pintype "passive"))
      (node (ref "C20") (pin "2") (pinfunction "2_2") (pintype "passive"))
      (node (ref "C21") (pin "1") (pinfunction "1_1") (pintype "passive"))
      (node (ref "C22") (pin "1") (pinfunction "1_1") (pintype "passive"))
      (node (ref "C23") (pin "2") (pinfunction "2_2") (pintype "passive"))
      (node (ref "C24") (pin "2") (pinfunction "2_2") (pintype "passive"))
      (node (ref "C25") (pin "1") (pinfunction "1_1") (pintype "passive"))
      (node (ref "C26") (pin "1") (pinfunction "1_1") (pintype "passive"))
      (node (ref "C27") (pin "1") (pinfunction "1_1") (pintype "passive"))
      (node (ref "C28") (pin "1") (pinfunction "1_1") (pintype "passive"))
      (node (ref "C29") (pin "1") (pinfunction "1_1") (pintype "passive"))
      (node (ref "C30") (pin "1") (pinfunction "1_1") (pintype "passive"))
      (node (ref "C31") (pin "1") (pinfunction "1_1") (pintype "passive"))
      (node (ref "C32") (pin "1") (pinfunction "1_1") (pintype "passive"))
      (node (ref "C33") (pin "1") (pinfunction "1_1") (pintype "passive"))
      (node (ref "C34") (pin "2") (pinfunction "2_2") (pintype "passive"))
      (node (ref "C35") (pin "2") (pinfunction "2_2") (pintype "passive"))
      (node (ref "C36") (pin "1") (pinfunction "1_1") (pintype "passive"))
      (node (ref "C37") (pin "2") (pinfunction "2_2") (pintype "passive"))
      (node (ref "C38") (pin "2") (pinfunction "2_2") (pintype "passive"))
      (node (ref "C39") (pin "1") (pinfunction "1_1") (pintype "passive"))
      (node (ref "C40") (pin "1") (pinfunction "1_1") (pintype "passive"))
      (node (ref "DAC1") (pin "10") (pinfunction "VREFL-F_10") (pintype "input"))
      (node (ref "DAC1") (pin "15") (pinfunction "GAIN_15") (pintype "input"))
      (node (ref "DAC1") (pin "18") (pinfunction "PDN_18") (pintype "input"))
      (node (ref "DAC1") (pin "22") (pinfunction "DGND_22") (pintype "bidirectional"))
      (node (ref "DAC1") (pin "25") (pinfunction "EP_25") (pintype "passive"))
      (node (ref "DAC1") (pin "3") (pinfunction "~{LDAC}_3") (pintype "bidirectional"))
      (node (ref "DAC1") (pin "4") (pinfunction "AGND_4") (pintype "bidirectional"))
      (node (ref "DAC1") (pin "6") (pinfunction "VREFL-S_6") (pintype "input"))
      (node (ref "DAC2") (pin "10") (pinfunction "VREFL-F_10") (pintype "input"))
      (node (ref "DAC2") (pin "14") (pinfunction "RSTSEL_14") (pintype "input"))
      (node (ref "DAC2") (pin "15") (pinfunction "GAIN_15") (pintype "input"))
      (node (ref "DAC2") (pin "18") (pinfunction "PDN_18") (pintype "input"))
      (node (ref "DAC2") (pin "22") (pinfunction "DGND_22") (pintype "bidirectional"))
      (node (ref "DAC2") (pin "25") (pinfunction "EP_25") (pintype "passive"))
      (node (ref "DAC2") (pin "3") (pinfunction "~{LDAC}_3") (pintype "bidirectional"))
      (node (ref "DAC2") (pin "4") (pinfunction "AGND_4") (pintype "bidirectional"))
      (node (ref "DAC2") (pin "6") (pinfunction "VREFL-S_6") (pintype "input"))
      (node (ref "LC (L) P") (pin "2") (pinfunction "Thermistor_2") (pintype "output"))
      (node (ref "LC (R)") (pin "13") (pinfunction "GND_13") (pintype "output"))
      (node (ref "LD") (pin "10") (pinfunction "RS-_10") (pintype "passive"))
      (node (ref "LD") (pin "12") (pinfunction "PD+_12") (pintype "passive"))
      (node (ref "LD") (pin "13") (pinfunction "PD-_13") (pintype "passive"))
      (node (ref "LD") (pin "7") (pinfunction "GND_7") (pintype "passive"))
      (node (ref "P3") (pin "1") (pinfunction "1_1") (pintype "passive"))
      (node (ref "P3") (pin "2") (pinfunction "2_2") (pintype "passive"))
      (node (ref "R10") (pin "1") (pinfunction "1_1") (pintype "passive"))
      (node (ref "R22") (pin "2") (pinfunction "2_2") (pintype "passive"))
      (node (ref "R9") (pin "1") (pinfunction "1_1") (pintype "passive"))
      (node (ref "Rpd1") (pin "2") (pinfunction "2_2") (pintype "passive"))
      (node (ref "TEC") (pin "13") (pinfunction "GND_13") (pintype "bidirectional"))
      (node (ref "U10") (pin "11") (pinfunction "GND_11") (pintype "bidirectional"))
      (node (ref "U10") (pin "12") (pinfunction "A1_12") (pintype "input"))
      (node (ref "U10") (pin "7") (pinfunction "A2_7") (pintype "input"))
      (node (ref "U10") (pin "8") (pinfunction "VSS_8") (pintype "bidirectional"))
      (node (ref "U11") (pin "2") (pinfunction "V-_2") (pintype "passive"))
      (node (ref "U11") (pin "3") (pinfunction "+INB_3") (pintype "passive"))
      (node (ref "U14") (pin "2") (pinfunction "V-_2") (pintype "passive"))
      (node (ref "U14") (pin "3") (pinfunction "+INB_3") (pintype "passive"))
      (node (ref "U6") (pin "13") (pinfunction "AVSS_13") (pintype "power_in"))
      (node (ref "U6") (pin "2") (pinfunction "DGND_2") (pintype "bidirectional"))
      (node (ref "U6") (pin "3") (pinfunction "CLK_3") (pintype "input"))
      (node (ref "U6") (pin "6") (pinfunction "REFN0/GPIO1_6") (pintype "bidirectional"))
      (node (ref "U6") (pin "8") (pinfunction "VREFCOM_8") (pintype "output"))
      (node (ref "U7") (pin "3") (pinfunction "GND_3") (pintype "bidirectional"))
      (node (ref "U7") (pin "4") (pinfunction "GNDS_4") (pintype "bidirectional"))
      (node (ref "U8") (pin "2") (pinfunction "V-_2") (pintype "passive"))
      (node (ref "U8") (pin "3") (pinfunction "+INB_3") (pintype "passive"))
      (node (ref "U9") (pin "2") (pinfunction "A_2") (pintype "passive"))
      (node (ref "U9") (pin "4") (pinfunction "GND_4") (pintype "passive"))
      (node (ref "U9") (pin "8") (pinfunction "AD1_8") (pintype "passive"))
    )
    (net (code "28") (name "Net-(DAC1-RSTSEL)") (class "Default")
      (node (ref "DAC1") (pin "14") (pinfunction "RSTSEL_14") (pintype "input"))
      (node (ref "R19") (pin "1") (pinfunction "1_1") (pintype "passive"))
    )
    (net (code "29") (name "Net-(DAC1-SDOSEL)") (class "Default")
      (node (ref "DAC1") (pin "20") (pinfunction "SDOSEL_20") (pintype "input"))
      (node (ref "R17") (pin "1") (pinfunction "1_1") (pintype "passive"))
    )
    (net (code "30") (name "Net-(DAC1-USB{slash}~{BTC})") (class "Default")
      (node (ref "DAC1") (pin "16") (pinfunction "USB/~{BTC}_16") (pintype "input"))
      (node (ref "R18") (pin "1") (pinfunction "1_1") (pintype "passive"))
    )
    (net (code "31") (name "Net-(DAC1-~{RST})") (class "Default")
      (node (ref "DAC1") (pin "17") (pinfunction "~{RST}_17") (pintype "input"))
      (node (ref "R20") (pin "1") (pinfunction "1_1") (pintype "passive"))
    )
    (net (code "32") (name "Net-(DAC2-SDOSEL)") (class "Default")
      (node (ref "DAC2") (pin "20") (pinfunction "SDOSEL_20") (pintype "input"))
      (node (ref "R4") (pin "1") (pinfunction "1_1") (pintype "passive"))
    )
    (net (code "33") (name "Net-(DAC2-USB{slash}~{BTC})") (class "Default")
      (node (ref "DAC2") (pin "16") (pinfunction "USB/~{BTC}_16") (pintype "input"))
      (node (ref "R16") (pin "1") (pinfunction "1_1") (pintype "passive"))
    )
    (net (code "34") (name "Net-(DAC2-~{RST})") (class "Default")
      (node (ref "DAC2") (pin "17") (pinfunction "~{RST}_17") (pintype "input"))
      (node (ref "R15") (pin "1") (pinfunction "1_1") (pintype "passive"))
    )
    (net (code "35") (name "Net-(LC (L) P-Mon_PD_Cathode)") (class "Default")
      (node (ref "LC (L) P") (pin "4") (pinfunction "Mon_PD_Cathode_4") (pintype "output"))
      (node (ref "P4") (pin "2") (pinfunction "2_2") (pintype "passive"))
    )
    (net (code "36") (name "Net-(LC (L) P-TEC+)") (class "Default")
      (node (ref "LC (L) P") (pin "1") (pinfunction "TEC+_1") (pintype "output"))
      (node (ref "TEC") (pin "12") (pinfunction "OutB_12") (pintype "passive"))
    )
    (net (code "37") (name "Net-(LC (R)-TEC-)") (class "Default")
      (node (ref "LC (R)") (pin "14") (pinfunction "TEC-_14") (pintype "output"))
      (node (ref "TEC") (pin "11") (pinfunction "OutA_11") (pintype "passive"))
    )
    (net (code "38") (name "Net-(LD-LIM)") (class "Default")
      (node (ref "LD") (pin "6") (pinfunction "LIM_6") (pintype "passive"))
      (node (ref "R21") (pin "1") (pinfunction "1_1") (pintype "passive"))
      (node (ref "U9") (pin "1") (pinfunction "B_1") (pintype "passive"))
      (node (ref "U9") (pin "10") (pinfunction "W_10") (pintype "passive"))
    )
    (net (code "39") (name "Net-(LD-MODE)") (class "Default")
      (node (ref "LD") (pin "5") (pinfunction "MODE_5") (pintype "passive"))
      (node (ref "R21") (pin "2") (pinfunction "2_2") (pintype "passive"))
    )
    (net (code "40") (name "Net-(LD-OUTB)") (class "Default")
      (node (ref "LD") (pin "8") (pinfunction "RS+_8") (pintype "passive"))
      (node (ref "LD") (pin "9") (pinfunction "OUTB_9") (pintype "passive"))
      (node (ref "R22") (pin "1") (pinfunction "1_1") (pintype "passive"))
    )
    (net (code "41") (name "Net-(TEC-+1v)") (class "Default")
      (node (ref "P2") (pin "4") (pinfunction "4_4") (pintype "passive"))
      (node (ref "TEC") (pin "6") (pinfunction "+1v_6") (pintype "passive"))
    )
    (net (code "42") (name "Net-(TEC-BIAS)") (class "Default")
      (node (ref "R13") (pin "1") (pinfunction "1_1") (pintype "passive"))
      (node (ref "TEC") (pin "10") (pinfunction "BIAS_10") (pintype "input"))
    )
    (net (code "43") (name "Net-(TEC-I)") (class "Default")
      (node (ref "P2") (pin "6") (pinfunction "6_6") (pintype "passive"))
      (node (ref "TEC") (pin "7") (pinfunction "I_7") (pintype "passive"))
    )
    (net (code "44") (name "Net-(TEC-LimA)") (class "Default")
      (node (ref "R9") (pin "2") (pinfunction "2_2") (pintype "passive"))
      (node (ref "TEC") (pin "3") (pinfunction "LimA_3") (pintype "bidirectional"))
    )
    (net (code "45") (name "Net-(TEC-LimB)") (class "Default")
      (node (ref "R10") (pin "2") (pinfunction "2_2") (pintype "passive"))
      (node (ref "TEC") (pin "4") (pinfunction "LimB_4") (pintype "bidirectional"))
    )
    (net (code "46") (name "Net-(TEC-P)") (class "Default")
      (node (ref "P2") (pin "2") (pinfunction "2_2") (pintype "passive"))
      (node (ref "TEC") (pin "5") (pinfunction "P_5") (pintype "passive"))
    )
    (net (code "47") (name "Net-(TEC-S+)") (class "Default")
      (node (ref "LC (L) P") (pin "5") (pinfunction "Thermistor_5") (pintype "output"))
      (node (ref "R8") (pin "1") (pinfunction "1_1") (pintype "passive"))
      (node (ref "TEC") (pin "9") (pinfunction "S+_9") (pintype "passive"))
      (node (ref "TP5") (pin "1") (pinfunction "1_1") (pintype "passive"))
      (node (ref "U8") (pin "1") (pinfunction "INA+_1") (pintype "passive"))
    )
    (net (code "48") (name "Net-(U6-VREFOUT)") (class "Default")
      (node (ref "C11") (pin "2") (pinfunction "2_2") (pintype "passive"))
      (node (ref "U6") (pin "7") (pinfunction "VREFOUT_7") (pintype "output"))
    )
    (net (code "49") (name "Net-(U7-NR)") (class "Default")
      (node (ref "C28") (pin "2") (pinfunction "2_2") (pintype "passive"))
      (node (ref "U7") (pin "1") (pinfunction "NR_1") (pintype "bidirectional"))
    )
    (net (code "50") (name "Net-(U8--INA)") (class "Default")
      (node (ref "R14") (pin "1") (pinfunction "1_1") (pintype "passive"))
      (node (ref "R7") (pin "1") (pinfunction "1_1") (pintype "passive"))
      (node (ref "U8") (pin "8") (pinfunction "-INA_8") (pintype "passive"))
    )
    (net (code "51") (name "Net-(U8--INB)") (class "Default")
      (node (ref "U8") (pin "4") (pinfunction "-INB_4") (pintype "passive"))
      (node (ref "U8") (pin "5") (pinfunction "OUTB_5") (pintype "passive"))
    )
    (net (code "52") (name "Net-(U8-OUTA)") (class "Default")
      (node (ref "R6") (pin "2") (pinfunction "2_2") (pintype "passive"))
      (node (ref "R7") (pin "2") (pinfunction "2_2") (pintype "passive"))
      (node (ref "U8") (pin "7") (pinfunction "OUTA_7") (pintype "passive"))
    )
    (net (code "53") (name "Net-(U10-HA)") (class "Default")
      (node (ref "P2") (pin "1") (pinfunction "1_1") (pintype "passive"))
      (node (ref "U10") (pin "1") (pinfunction "HA_1") (pintype "passive"))
    )
    (net (code "54") (name "Net-(U10-HB)") (class "Default")
      (node (ref "P2") (pin "5") (pinfunction "5_5") (pintype "passive"))
      (node (ref "U10") (pin "4") (pinfunction "HB_4") (pintype "passive"))
      (node (ref "U10") (pin "6") (pinfunction "WB_6") (pintype "passive"))
    )
    (net (code "55") (name "Net-(U10-LA)") (class "Default")
      (node (ref "P2") (pin "3") (pinfunction "3_3") (pintype "passive"))
      (node (ref "U10") (pin "2") (pinfunction "LA_2") (pintype "passive"))
      (node (ref "U10") (pin "3") (pinfunction "WA_3") (pintype "passive"))
      (node (ref "U10") (pin "5") (pinfunction "LB_5") (pintype "passive"))
    )
    (net (code "56") (name "Net-(U11--INA)") (class "Default")
      (node (ref "R11") (pin "2") (pinfunction "2_2") (pintype "passive"))
      (node (ref "U11") (pin "7") (pinfunction "OUTA_7") (pintype "passive"))
      (node (ref "U11") (pin "8") (pinfunction "-INA_8") (pintype "passive"))
    )
    (net (code "57") (name "Net-(U11--INB)") (class "Default")
      (node (ref "U11") (pin "4") (pinfunction "-INB_4") (pintype "passive"))
      (node (ref "U11") (pin "5") (pinfunction "OUTB_5") (pintype "passive"))
    )
    (net (code "58") (name "Net-(U14--INA)") (class "Default")
      (node (ref "R12") (pin "2") (pinfunction "2_2") (pintype "passive"))
      (node (ref "U14") (pin "7") (pinfunction "OUTA_7") (pintype "passive"))
      (node (ref "U14") (pin "8") (pinfunction "-INA_8") (pintype "passive"))
    )
    (net (code "59") (name "Net-(U14--INB)") (class "Default")
      (node (ref "U14") (pin "4") (pinfunction "-INB_4") (pintype "passive"))
      (node (ref "U14") (pin "5") (pinfunction "OUTB_5") (pintype "passive"))
    )
    (net (code "60") (name "unconnected-(DAC1-NC-Pad12)") (class "Default")
      (node (ref "DAC1") (pin "12") (pinfunction "NC_12") (pintype "passive+no_connect"))
    )
    (net (code "61") (name "unconnected-(DAC1-NC-Pad13)") (class "Default")
      (node (ref "DAC1") (pin "13") (pinfunction "NC_13") (pintype "passive+no_connect"))
    )
    (net (code "62") (name "unconnected-(DAC2-NC-Pad12)") (class "Default")
      (node (ref "DAC2") (pin "12") (pinfunction "NC_12") (pintype "passive+no_connect"))
    )
    (net (code "63") (name "unconnected-(DAC2-NC-Pad13)") (class "Default")
      (node (ref "DAC2") (pin "13") (pinfunction "NC_13") (pintype "passive+no_connect"))
    )
    (net (code "64") (name "unconnected-(LC (L) P-NC-Pad6)") (class "Default")
      (node (ref "LC (L) P") (pin "6") (pinfunction "NC_6") (pintype "output+no_connect"))
    )
    (net (code "65") (name "unconnected-(LC (L) P-NC-Pad7)") (class "Default")
      (node (ref "LC (L) P") (pin "7") (pinfunction "NC_7") (pintype "output+no_connect"))
    )
    (net (code "66") (name "unconnected-(LC (R)-NC-Pad8)") (class "Default")
      (node (ref "LC (R)") (pin "8") (pinfunction "NC_8") (pintype "output+no_connect"))
    )
    (net (code "67") (name "unconnected-(LC (R)-NC-Pad9)") (class "Default")
      (node (ref "LC (R)") (pin "9") (pinfunction "NC_9") (pintype "output+no_connect"))
    )
    (net (code "68") (name "unconnected-(LC (R)-NC-Pad12)") (class "Default")
      (node (ref "LC (R)") (pin "12") (pinfunction "NC_12") (pintype "output+no_connect"))
    )
    (net (code "69") (name "unconnected-(LD-PMON-Pad4)") (class "Default")
      (node (ref "LD") (pin "4") (pinfunction "PMON_4") (pintype "passive+no_connect"))
    )
    (net (code "70") (name "unconnected-(U6-AIN3{slash}IEXC{slash}GPIO3-Pad12)") (class "Default")
      (node (ref "U6") (pin "12") (pinfunction "AIN3/IEXC/GPIO3_12") (pintype "bidirectional+no_connect"))
    )
    (net (code "71") (name "unconnected-(U7-IC-Pad5)") (class "Default")
      (node (ref "U7") (pin "5") (pinfunction "IC_5") (pintype "passive+no_connect"))
    )
    (net (code "72") (name "unconnected-(U7-IC-Pad8)") (class "Default")
      (node (ref "U7") (pin "8") (pinfunction "IC_8") (pintype "passive+no_connect"))
    )
    (net (code "73") (name "unconnected-(U9-NC-Pad9)") (class "Default")
      (node (ref "U9") (pin "9") (pinfunction "NC_9") (pintype "passive+no_connect"))
    )
  )
)
